# microcontroller.net
KiCad netlist of a schematic drawn in Altium Designer
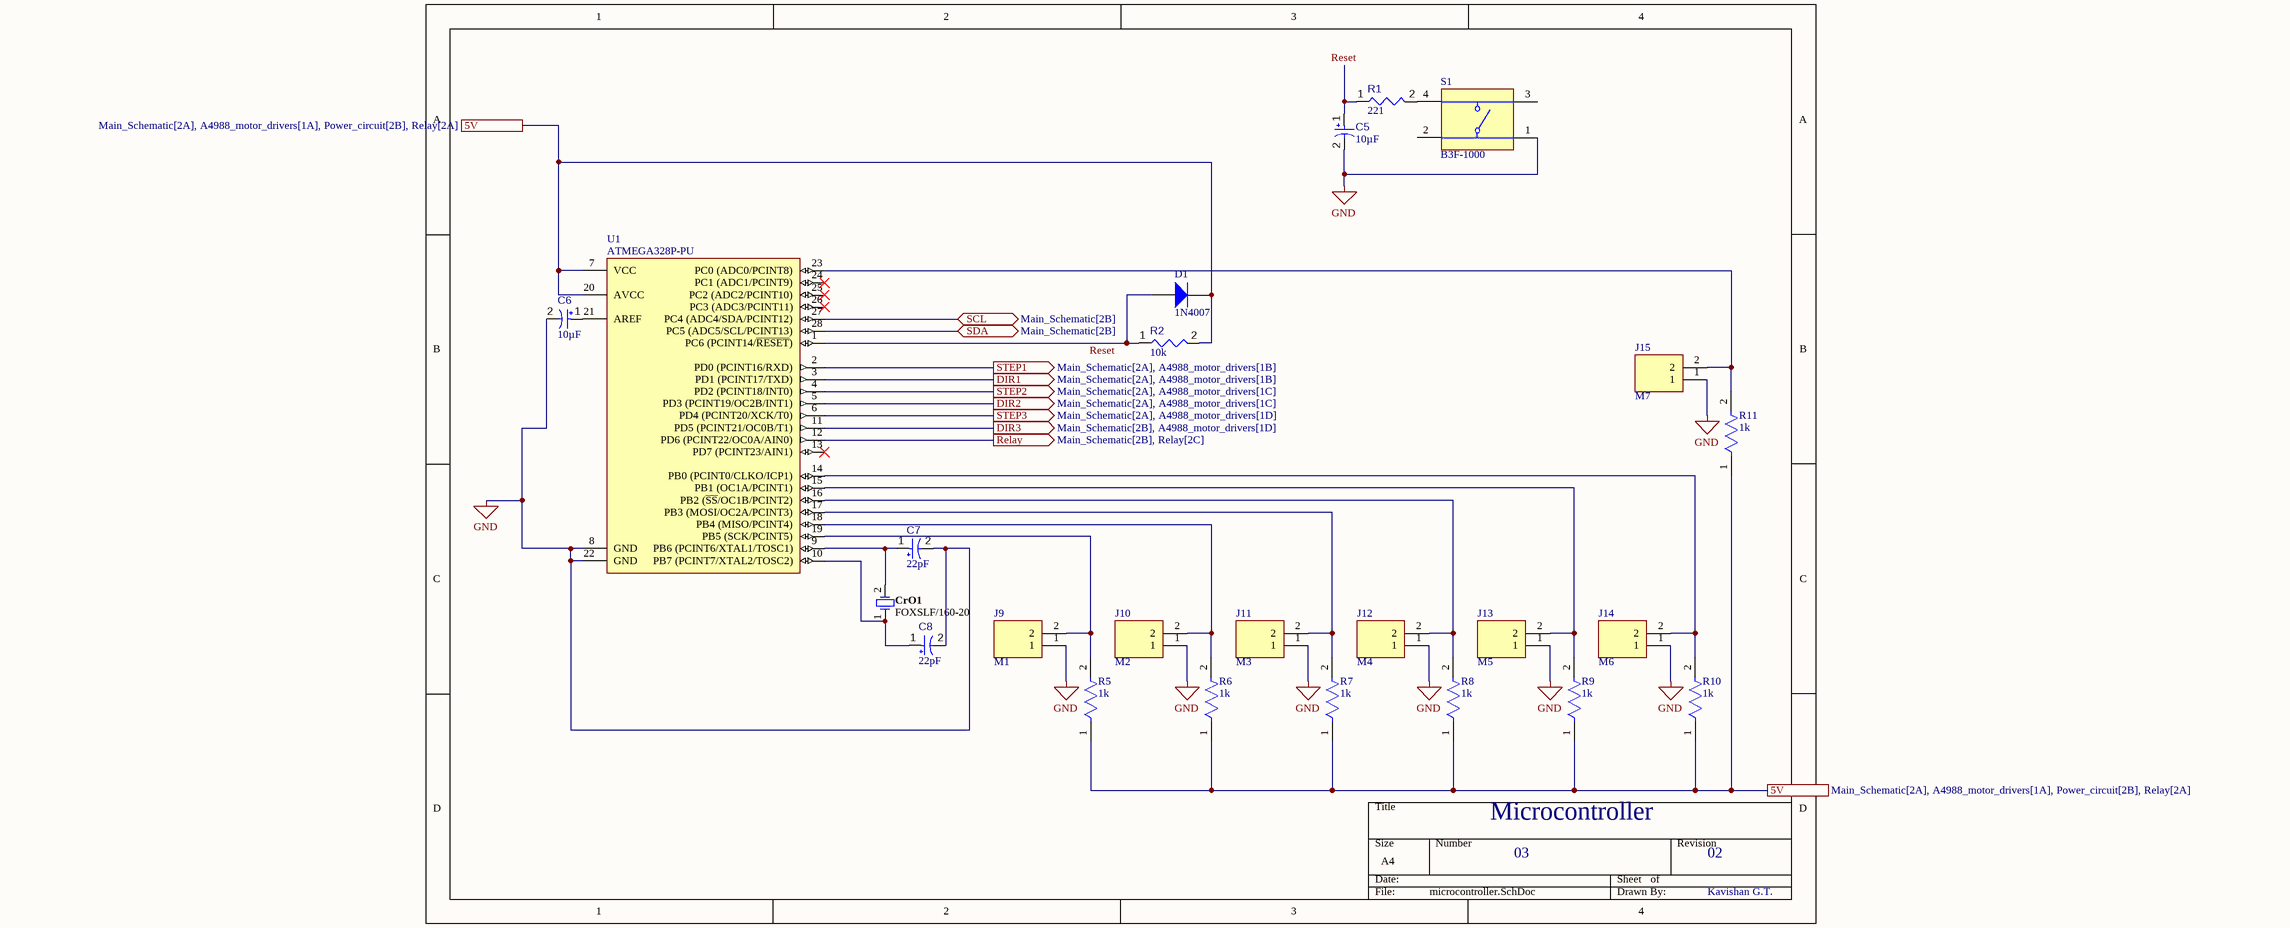
[diagram p0: microcontroller.SchDoc]

(export (version "E")
  (design (tool "Eeschema 10.0.6"))
  (components
    (comp (ref "C5")
      (value "10µF")
      (footprint "CAPPR55-200-1100X500X1200")
      (description "Aluminum Electrolytic Capacitor, 10 uF, +/- 20%, 50 V, -40 to 85 degC, 2-Pin THD, RoHS, Bulk")
      (fields (field (name "MANUFACTURER") "Panasonic") (field (name "TOLERANCE") "20%"))
      (libsource (lib "") (part "CAP-P-2_1"))
    )
    (comp (ref "C6")
      (value "10µF")
      (footprint "CAPPR55-200-1100X500X1200")
      (description "Aluminum Electrolytic Capacitor, 10 uF, +/- 20%, 50 V, -40 to 85 degC, 2-Pin THD, RoHS, Bulk")
      (fields (field (name "MANUFACTURER") "Panasonic") (field (name "TOLERANCE") "20%"))
      (libsource (lib "") (part "CAP-P-2_2"))
    )
    (comp (ref "C7")
      (value "22pF")
      (footprint "CAPPR55-200-1100X500X1200")
      (description "Aluminum Electrolytic Capacitor, 10 uF, +/- 20%, 50 V, -40 to 85 degC, 2-Pin THD, RoHS, Bulk")
      (fields (field (name "MANUFACTURER") "Panasonic") (field (name "TOLERANCE") "20%"))
      (libsource (lib "University of Moratuwa") (part "CAP-P-2"))
    )
    (comp (ref "C8")
      (value "22pF")
      (footprint "CAPPR55-200-1100X500X1200")
      (description "Aluminum Electrolytic Capacitor, 10 uF, +/- 20%, 50 V, -40 to 85 degC, 2-Pin THD, RoHS, Bulk")
      (fields (field (name "MANUFACTURER") "Panasonic") (field (name "TOLERANCE") "20%"))
      (libsource (lib "University of Moratuwa") (part "CAP-P-2"))
    )
    (comp (ref "CrO1")
      (value "FOXSLF/160-20")
      (footprint "FOX-FOXSLF160-20")
      (description "Resistance Weld Thru-Hole Crystal, 16 MHz, -20 to 70 degC, 2-Pin THD, RoHS, Bulk")
      (fields (field (name "TOLERANCE") "1%"))
      (libsource (lib "Altium Content Vault") (part "XTAL-1-2-2"))
    )
    (comp (ref "D1")
      (value "1N4007")
      (footprint "FAIR-DO-41-2")
      (description "General Purpose Rectifier, 1.1 V, 1.0 A, -55 to 175 degC, 2-Pin DO-41, RoHS, Tape and Reel")
      (fields (field (name "MANUFACTURER") "Fairchild"))
      (libsource (lib "University of Moratuwa") (part "KESE-D_K1A2-2"))
    )
    (comp (ref "J9")
      (value "M1")
      (footprint "SamacSys:SHDR2W64P0X250_1X2_750X380X600P")
      (description "Connector")
      (fields (field (name "MANUFACTURER_PART_NUMBER") "B2B-EH-A"))
      (libsource (lib "*") (part "B2B-EH-A"))
    )
    (comp (ref "J10")
      (value "M2")
      (footprint "SamacSys:SHDR2W64P0X250_1X2_750X380X600P")
      (description "Connector")
      (fields (field (name "MANUFACTURER_PART_NUMBER") "B2B-EH-A"))
      (libsource (lib "*") (part "B2B-EH-A"))
    )
    (comp (ref "J11")
      (value "M3")
      (footprint "SamacSys:SHDR2W64P0X250_1X2_750X380X600P")
      (description "Connector")
      (fields (field (name "MANUFACTURER_PART_NUMBER") "B2B-EH-A"))
      (libsource (lib "*") (part "B2B-EH-A"))
    )
    (comp (ref "J12")
      (value "M4")
      (footprint "SamacSys:SHDR2W64P0X250_1X2_750X380X600P")
      (description "Connector")
      (fields (field (name "MANUFACTURER_PART_NUMBER") "B2B-EH-A"))
      (libsource (lib "*") (part "B2B-EH-A"))
    )
    (comp (ref "J13")
      (value "M5")
      (footprint "SamacSys:SHDR2W64P0X250_1X2_750X380X600P")
      (description "Connector")
      (fields (field (name "MANUFACTURER_PART_NUMBER") "B2B-EH-A"))
      (libsource (lib "*") (part "B2B-EH-A"))
    )
    (comp (ref "J14")
      (value "M6")
      (footprint "SamacSys:SHDR2W64P0X250_1X2_750X380X600P")
      (description "Connector")
      (fields (field (name "MANUFACTURER_PART_NUMBER") "B2B-EH-A"))
      (libsource (lib "*") (part "B2B-EH-A"))
    )
    (comp (ref "J15")
      (value "M7")
      (footprint "SamacSys:SHDR2W64P0X250_1X2_750X380X600P")
      (description "Connector")
      (fields (field (name "MANUFACTURER_PART_NUMBER") "B2B-EH-A"))
      (libsource (lib "*") (part "B2B-EH-A"))
    )
    (comp (ref "R1")
      (value "221")
      (footprint "RESA60-630X240")
      (description "Axial Resistor, 221 Ohm, +/- 1%, 250 mW, -55 to 155 degC, 2-Pin THD, RoHS, Bulk")
      (fields (field (name "POWER") "250mW") (field (name "TOLERANCE") "1%"))
      (libsource (lib "University of Moratuwa") (part "RES-2"))
    )
    (comp (ref "R2")
      (value "10k")
      (footprint "RESA60-630X240")
      (description "Axial Resistor, 10 KOhm, +/- 1%, 0.25 W, -55 to 155 degC, 2-Pin THD, RoHS, Bulk")
      (fields (field (name "TOLERANCE") "1%") (field (name "POWER") "250mW"))
      (libsource (lib "University of Moratuwa") (part "RES-2"))
    )
    (comp (ref "R5")
      (value "1k")
      (footprint "FP-MFR-25-MFG")
      (description "RES 1.18K OHM 1/4W 1% AXIAL")
      (fields (field (name "MANUFACTURER") "Yageo") (field (name "TOLERANCE") "1%"))
      (libsource (lib "Altium Content Vault") (part "1029c3af85768c4190bb7ad29bc67b5"))
    )
    (comp (ref "R6")
      (value "1k")
      (footprint "FP-MFR-25-MFG")
      (description "RES 1.18K OHM 1/4W 1% AXIAL")
      (fields (field (name "MANUFACTURER") "Yageo") (field (name "TOLERANCE") "1%"))
      (libsource (lib "Altium Content Vault") (part "1029c3af85768c4190bb7ad29bc67b5"))
    )
    (comp (ref "R7")
      (value "1k")
      (footprint "FP-MFR-25-MFG")
      (description "RES 1.18K OHM 1/4W 1% AXIAL")
      (fields (field (name "MANUFACTURER") "Yageo") (field (name "TOLERANCE") "1%"))
      (libsource (lib "Altium Content Vault") (part "1029c3af85768c4190bb7ad29bc67b5"))
    )
    (comp (ref "R8")
      (value "1k")
      (footprint "FP-MFR-25-MFG")
      (description "RES 1.18K OHM 1/4W 1% AXIAL")
      (fields (field (name "MANUFACTURER") "Yageo") (field (name "TOLERANCE") "1%"))
      (libsource (lib "Altium Content Vault") (part "1029c3af85768c4190bb7ad29bc67b5"))
    )
    (comp (ref "R9")
      (value "1k")
      (footprint "FP-MFR-25-MFG")
      (description "RES 1.18K OHM 1/4W 1% AXIAL")
      (fields (field (name "MANUFACTURER") "Yageo") (field (name "TOLERANCE") "1%"))
      (libsource (lib "Altium Content Vault") (part "1029c3af85768c4190bb7ad29bc67b5"))
    )
    (comp (ref "R10")
      (value "1k")
      (footprint "FP-MFR-25-MFG")
      (description "RES 1.18K OHM 1/4W 1% AXIAL")
      (fields (field (name "MANUFACTURER") "Yageo") (field (name "TOLERANCE") "1%"))
      (libsource (lib "Altium Content Vault") (part "1029c3af85768c4190bb7ad29bc67b5"))
    )
    (comp (ref "R11")
      (value "1k")
      (footprint "FP-MFR-25-MFG")
      (description "RES 1.18K OHM 1/4W 1% AXIAL")
      (fields (field (name "MANUFACTURER") "Yageo") (field (name "TOLERANCE") "1%"))
      (libsource (lib "Altium Content Vault") (part "1029c3af85768c4190bb7ad29bc67b5"))
    )
    (comp (ref "S1")
      (value "B3F-1000")
      (footprint "OMRON-B3F-1000-4_V")
      (description "Tactile Switch, SPST-NO, 0.05 A, 24 V, -25 to 70 degC, 4-Pin THD, RoHS, Bulk")
      (fields (field (name "MANUFACTURER") "Omron Electronic Components"))
      (libsource (lib "University of Moratuwa") (part "SW-SPST-4_A"))
    )
    (comp (ref "U1")
      (value "ATMEGA328P-PU")
      (footprint "ATML-28P3")
      (fields (field (name "MANUFACTURER") "Atmel"))
      (libsource (lib "University of Moratuwa") (part "MC-8B-ATM48-IL28"))
    )
  )
  (nets
    (net (code "1") (name "/5V") (class "Default")
      (node (ref "D1") (pin "1") (pinfunction "K_1") (pintype "passive"))
      (node (ref "R10") (pin "1") (pinfunction "1_1") (pintype "passive"))
      (node (ref "R11") (pin "1") (pinfunction "1_1") (pintype "passive"))
      (node (ref "R2") (pin "2") (pinfunction "2_2") (pintype "passive"))
      (node (ref "R5") (pin "1") (pinfunction "1_1") (pintype "passive"))
      (node (ref "R6") (pin "1") (pinfunction "1_1") (pintype "passive"))
      (node (ref "R7") (pin "1") (pinfunction "1_1") (pintype "passive"))
      (node (ref "R8") (pin "1") (pinfunction "1_1") (pintype "passive"))
      (node (ref "R9") (pin "1") (pinfunction "1_1") (pintype "passive"))
      (node (ref "U1") (pin "20") (pinfunction "AVCC_20") (pintype "power_in"))
      (node (ref "U1") (pin "7") (pinfunction "VCC_7") (pintype "power_in"))
    )
    (net (code "2") (name "/DIR1") (class "Default")
      (node (ref "U1") (pin "3") (pinfunction "PD1_(PCINT17/TXD)_3") (pintype "output"))
    )
    (net (code "3") (name "/DIR2") (class "Default")
      (node (ref "U1") (pin "5") (pinfunction "PD3_(PCINT19/OC2B/INT1)_5") (pintype "output"))
    )
    (net (code "4") (name "/DIR3") (class "Default")
      (node (ref "U1") (pin "11") (pinfunction "PD5_(PCINT21/OC0B/T1)_11") (pintype "output"))
    )
    (net (code "5") (name "/Relay") (class "Default")
      (node (ref "U1") (pin "12") (pinfunction "PD6_(PCINT22/OC0A/AIN0)_12") (pintype "output"))
    )
    (net (code "6") (name "/Reset") (class "Default")
      (node (ref "C5") (pin "1") (pinfunction "1_1") (pintype "passive"))
      (node (ref "D1") (pin "2") (pinfunction "A_2") (pintype "passive"))
      (node (ref "R1") (pin "1") (pinfunction "1_1") (pintype "passive"))
      (node (ref "R2") (pin "1") (pinfunction "1_1") (pintype "passive"))
      (node (ref "U1") (pin "1") (pinfunction "PC6_(PCINT14/~{RESET})_1") (pintype "bidirectional"))
    )
    (net (code "7") (name "/SCL") (class "Default")
      (node (ref "U1") (pin "27") (pinfunction "PC4_(ADC4/SDA/PCINT12)_27") (pintype "bidirectional"))
    )
    (net (code "8") (name "/SDA") (class "Default")
      (node (ref "U1") (pin "28") (pinfunction "PC5_(ADC5/SCL/PCINT13)_28") (pintype "bidirectional"))
    )
    (net (code "9") (name "/STEP1") (class "Default")
      (node (ref "U1") (pin "2") (pinfunction "PD0_(PCINT16/RXD)_2") (pintype "output"))
    )
    (net (code "10") (name "/STEP2") (class "Default")
      (node (ref "U1") (pin "4") (pinfunction "PD2_(PCINT18/INT0)_4") (pintype "output"))
    )
    (net (code "11") (name "/STEP3") (class "Default")
      (node (ref "U1") (pin "6") (pinfunction "PD4_(PCINT20/XCK/T0)_6") (pintype "output"))
    )
    (net (code "12") (name "GND") (class "Default")
      (node (ref "C5") (pin "2") (pinfunction "2_2") (pintype "passive"))
      (node (ref "C6") (pin "2") (pinfunction "2_2") (pintype "passive"))
      (node (ref "C7") (pin "2") (pinfunction "2_2") (pintype "passive"))
      (node (ref "C8") (pin "2") (pinfunction "2_2") (pintype "passive"))
      (node (ref "J10") (pin "1") (pinfunction "1_1") (pintype "passive"))
      (node (ref "J11") (pin "1") (pinfunction "1_1") (pintype "passive"))
      (node (ref "J12") (pin "1") (pinfunction "1_1") (pintype "passive"))
      (node (ref "J13") (pin "1") (pinfunction "1_1") (pintype "passive"))
      (node (ref "J14") (pin "1") (pinfunction "1_1") (pintype "passive"))
      (node (ref "J15") (pin "1") (pinfunction "1_1") (pintype "passive"))
      (node (ref "J9") (pin "1") (pinfunction "1_1") (pintype "passive"))
      (node (ref "S1") (pin "1") (pinfunction "1_1") (pintype "passive"))
      (node (ref "U1") (pin "22") (pinfunction "GND_22") (pintype "power_in"))
      (node (ref "U1") (pin "8") (pinfunction "GND_8") (pintype "power_in"))
    )
    (net (code "13") (name "Net-(R1-Pad2)") (class "Default")
      (node (ref "R1") (pin "2") (pinfunction "2_2") (pintype "passive"))
      (node (ref "S1") (pin "4") (pinfunction "4_4") (pintype "passive"))
    )
    (net (code "14") (name "Net-(U1-AREF)") (class "Default")
      (node (ref "C6") (pin "1") (pinfunction "1_1") (pintype "passive"))
      (node (ref "U1") (pin "21") (pinfunction "AREF_21") (pintype "power_in"))
    )
    (net (code "15") (name "Net-(U1-PB0_(PCINT0{slash}CLKO{slash}ICP1))") (class "Default")
      (node (ref "J14") (pin "2") (pinfunction "2_2") (pintype "passive"))
      (node (ref "R10") (pin "2") (pinfunction "2_2") (pintype "passive"))
      (node (ref "U1") (pin "14") (pinfunction "PB0_(PCINT0/CLKO/ICP1)_14") (pintype "bidirectional"))
    )
    (net (code "16") (name "Net-(U1-PB1_(OC1A{slash}PCINT1))") (class "Default")
      (node (ref "J13") (pin "2") (pinfunction "2_2") (pintype "passive"))
      (node (ref "R9") (pin "2") (pinfunction "2_2") (pintype "passive"))
      (node (ref "U1") (pin "15") (pinfunction "PB1_(OC1A/PCINT1)_15") (pintype "bidirectional"))
    )
    (net (code "17") (name "Net-(U1-PB2_(~{SS}{slash}OC1B{slash}PCINT2))") (class "Default")
      (node (ref "J12") (pin "2") (pinfunction "2_2") (pintype "passive"))
      (node (ref "R8") (pin "2") (pinfunction "2_2") (pintype "passive"))
      (node (ref "U1") (pin "16") (pinfunction "PB2_(~{SS}/OC1B/PCINT2)_16") (pintype "bidirectional"))
    )
    (net (code "18") (name "Net-(U1-PB3_(MOSI{slash}OC2A{slash}PCINT3))") (class "Default")
      (node (ref "J11") (pin "2") (pinfunction "2_2") (pintype "passive"))
      (node (ref "R7") (pin "2") (pinfunction "2_2") (pintype "passive"))
      (node (ref "U1") (pin "17") (pinfunction "PB3_(MOSI/OC2A/PCINT3)_17") (pintype "bidirectional"))
    )
    (net (code "19") (name "Net-(U1-PB4_(MISO{slash}PCINT4))") (class "Default")
      (node (ref "J10") (pin "2") (pinfunction "2_2") (pintype "passive"))
      (node (ref "R6") (pin "2") (pinfunction "2_2") (pintype "passive"))
      (node (ref "U1") (pin "18") (pinfunction "PB4_(MISO/PCINT4)_18") (pintype "bidirectional"))
    )
    (net (code "20") (name "Net-(U1-PB5_(SCK{slash}PCINT5))") (class "Default")
      (node (ref "J9") (pin "2") (pinfunction "2_2") (pintype "passive"))
      (node (ref "R5") (pin "2") (pinfunction "2_2") (pintype "passive"))
      (node (ref "U1") (pin "19") (pinfunction "PB5_(SCK/PCINT5)_19") (pintype "bidirectional"))
    )
    (net (code "21") (name "Net-(U1-PB6_(PCINT6{slash}XTAL1{slash}TOSC1))") (class "Default")
      (node (ref "C7") (pin "1") (pinfunction "1_1") (pintype "passive"))
      (node (ref "CrO1") (pin "2") (pinfunction "2_2") (pintype "passive"))
      (node (ref "U1") (pin "9") (pinfunction "PB6_(PCINT6/XTAL1/TOSC1)_9") (pintype "bidirectional"))
    )
    (net (code "22") (name "Net-(U1-PB7_(PCINT7{slash}XTAL2{slash}TOSC2))") (class "Default")
      (node (ref "C8") (pin "1") (pinfunction "1_1") (pintype "passive"))
      (node (ref "CrO1") (pin "1") (pinfunction "1_1") (pintype "passive"))
      (node (ref "U1") (pin "10") (pinfunction "PB7_(PCINT7/XTAL2/TOSC2)_10") (pintype "bidirectional"))
    )
    (net (code "23") (name "Net-(U1-PC0_(ADC0{slash}PCINT8))") (class "Default")
      (node (ref "J15") (pin "2") (pinfunction "2_2") (pintype "passive"))
      (node (ref "R11") (pin "2") (pinfunction "2_2") (pintype "passive"))
      (node (ref "U1") (pin "23") (pinfunction "PC0_(ADC0/PCINT8)_23") (pintype "bidirectional"))
    )
    (net (code "24") (name "unconnected-(S1-Pad2)") (class "Default")
      (node (ref "S1") (pin "2") (pinfunction "2_2") (pintype "passive"))
    )
    (net (code "25") (name "unconnected-(S1-Pad3)") (class "Default")
      (node (ref "S1") (pin "3") (pinfunction "3_3") (pintype "passive"))
    )
    (net (code "26") (name "unconnected-(U1-PC1_(ADC1{slash}PCINT9)-Pad24)") (class "Default")
      (node (ref "U1") (pin "24") (pinfunction "PC1_(ADC1/PCINT9)_24") (pintype "bidirectional+no_connect"))
    )
    (net (code "27") (name "unconnected-(U1-PC2_(ADC2{slash}PCINT10)-Pad25)") (class "Default")
      (node (ref "U1") (pin "25") (pinfunction "PC2_(ADC2/PCINT10)_25") (pintype "bidirectional+no_connect"))
    )
    (net (code "28") (name "unconnected-(U1-PC3_(ADC3{slash}PCINT11)-Pad26)") (class "Default")
      (node (ref "U1") (pin "26") (pinfunction "PC3_(ADC3/PCINT11)_26") (pintype "bidirectional+no_connect"))
    )
    (net (code "29") (name "unconnected-(U1-PD7_(PCINT23{slash}AIN1)-Pad13)") (class "Default")
      (node (ref "U1") (pin "13") (pinfunction "PD7_(PCINT23/AIN1)_13") (pintype "bidirectional+no_connect"))
    )
  )
)
